# Sheet1.net
KiCad netlist of a schematic drawn in Altium Designer
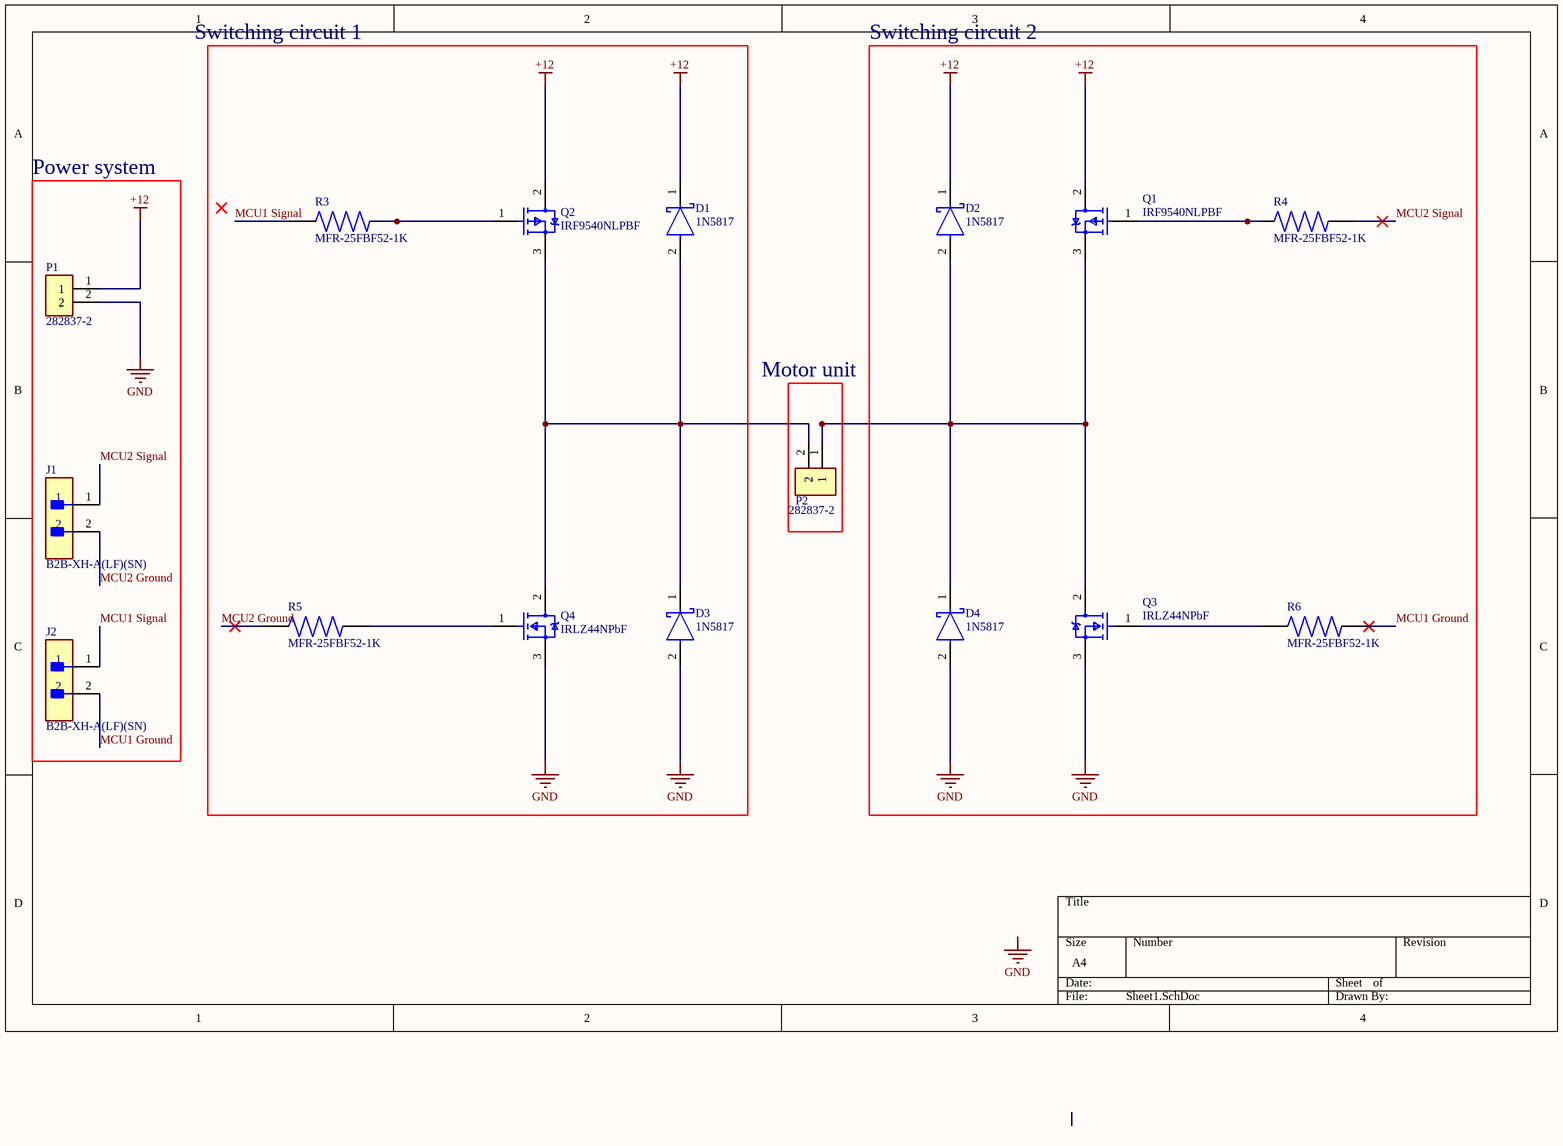
[diagram p0: Sheet1.SchDoc]

(export (version "E")
  (design (tool "Eeschema 10.0.6"))
  (components
    (comp (ref "D1")
      (value "1N5817")
      (footprint "FP-DO-41-MFG")
      (description "DIODE SCHOTTKY 20V 1A DO41")
      (libsource (lib "Altium Content Vault") (part "1d6ec82d83fb6aee721767c19dac4b9"))
    )
    (comp (ref "D2")
      (value "1N5817")
      (footprint "FP-DO-41-MFG")
      (description "DIODE SCHOTTKY 20V 1A DO41")
      (libsource (lib "Altium Content Vault") (part "1d6ec82d83fb6aee721767c19dac4b9"))
    )
    (comp (ref "D3")
      (value "1N5817")
      (footprint "FP-DO-41-MFG")
      (description "DIODE SCHOTTKY 20V 1A DO41")
      (libsource (lib "Altium Content Vault") (part "1d6ec82d83fb6aee721767c19dac4b9"))
    )
    (comp (ref "D4")
      (value "1N5817")
      (footprint "FP-DO-41-MFG")
      (description "DIODE SCHOTTKY 20V 1A DO41")
      (libsource (lib "Altium Content Vault") (part "1d6ec82d83fb6aee721767c19dac4b9"))
    )
    (comp (ref "J1")
      (value "B2B-XH-A(LF)(SN)")
      (footprint "FP-B2B-XH-A_LF_SN-MFG")
      (description "CONN HEADER VERT 2POS 2.5MM")
      (libsource (lib "Altium Content Vault") (part "3bc925449376181038e59eaffc5286c"))
    )
    (comp (ref "J2")
      (value "B2B-XH-A(LF)(SN)")
      (footprint "FP-B2B-XH-A_LF_SN-MFG")
      (description "CONN HEADER VERT 2POS 2.5MM")
      (libsource (lib "Altium Content Vault") (part "3bc925449376181038e59eaffc5286c"))
    )
    (comp (ref "P1")
      (value "282837-2")
      (footprint "TE_282837-2")
      (fields (field (name "MF") "TE Connectivity"))
      (libsource (lib "282837-2 (1)") (part "282837-2"))
    )
    (comp (ref "P2")
      (value "282837-2")
      (footprint "TE_282837-2")
      (fields (field (name "MF") "TE Connectivity"))
      (libsource (lib "282837-2 (1)") (part "282837-2"))
    )
    (comp (ref "Q1")
      (value "IRF9540NLPBF")
      (footprint "FP-PG-TO262-3-MFG")
      (description "MOSFET P-CH 100V 23A TO262-3")
      (libsource (lib "Altium Content Vault") (part "38cbee71a1bce1ebb3b8a3a9639eda0"))
    )
    (comp (ref "Q2")
      (value "IRF9540NLPBF")
      (footprint "FP-PG-TO262-3-MFG")
      (description "MOSFET P-CH 100V 23A TO262-3")
      (libsource (lib "Altium Content Vault") (part "38cbee71a1bce1ebb3b8a3a9639eda0"))
    )
    (comp (ref "Q3")
      (value "IRLZ44NPbF")
      (footprint "FP-PG-TO220-3-MFG")
      (description "MOSFET N-CH 55V 47A TO220AB")
      (libsource (lib "Altium Content Vault") (part "b09f7f152735e370c1ea22a33fa83d6"))
    )
    (comp (ref "Q4")
      (value "IRLZ44NPbF")
      (footprint "FP-PG-TO220-3-MFG")
      (description "MOSFET N-CH 55V 47A TO220AB")
      (libsource (lib "Altium Content Vault") (part "b09f7f152735e370c1ea22a33fa83d6"))
    )
    (comp (ref "R3")
      (value "MFR-25FBF52-1K")
      (footprint "RESAD1100W55L680D260")
      (description "10.2 kOhms Â±1% 0.25W, 1/4W Through Hole Resistor Axial - Metal Film")
      (fields (field (name "MF") "Yageo") (field (name "MP") "MFR-25FBF52-10K"))
      (libsource (lib "MFR-25FBF52-10K (1)") (part "MFR-25FBF52-10K"))
    )
    (comp (ref "R4")
      (value "MFR-25FBF52-1K")
      (footprint "RESAD1100W55L680D260")
      (description "10.2 kOhms Â±1% 0.25W, 1/4W Through Hole Resistor Axial - Metal Film")
      (fields (field (name "MF") "Yageo") (field (name "MP") "MFR-25FBF52-10K"))
      (libsource (lib "MFR-25FBF52-10K (1)") (part "MFR-25FBF52-10K"))
    )
    (comp (ref "R5")
      (value "MFR-25FBF52-1K")
      (footprint "RESAD1100W55L680D260")
      (description "10.2 kOhms Â±1% 0.25W, 1/4W Through Hole Resistor Axial - Metal Film")
      (fields (field (name "MF") "Yageo") (field (name "MP") "MFR-25FBF52-10K"))
      (libsource (lib "MFR-25FBF52-10K (1)") (part "MFR-25FBF52-10K"))
    )
    (comp (ref "R6")
      (value "MFR-25FBF52-1K")
      (footprint "RESAD1100W55L680D260")
      (description "10.2 kOhms Â±1% 0.25W, 1/4W Through Hole Resistor Axial - Metal Film")
      (fields (field (name "MF") "Yageo") (field (name "MP") "MFR-25FBF52-10K"))
      (libsource (lib "MFR-25FBF52-10K (1)") (part "MFR-25FBF52-10K"))
    )
  )
  (nets
    (net (code "1") (name "+12") (class "Default")
      (node (ref "D1") (pin "1") (pinfunction "C_1") (pintype "passive"))
      (node (ref "D2") (pin "1") (pinfunction "C_1") (pintype "passive"))
      (node (ref "P1") (pin "1") (pinfunction "1_1") (pintype "passive"))
      (node (ref "Q1") (pin "2") (pinfunction "Drain_2") (pintype "passive"))
      (node (ref "Q2") (pin "2") (pinfunction "Drain_2") (pintype "passive"))
    )
    (net (code "2") (name "/MCU1 Ground") (class "Default")
      (node (ref "J2") (pin "2") (pinfunction "2_2") (pintype "passive"))
      (node (ref "R6") (pin "2") (pinfunction "2_2") (pintype "passive"))
    )
    (net (code "3") (name "/MCU1 Signal") (class "Default")
      (node (ref "J2") (pin "1") (pinfunction "1_1") (pintype "passive"))
      (node (ref "R3") (pin "1") (pinfunction "1_1") (pintype "passive"))
    )
    (net (code "4") (name "/MCU2 Ground") (class "Default")
      (node (ref "J1") (pin "2") (pinfunction "2_2") (pintype "passive"))
      (node (ref "R5") (pin "1") (pinfunction "1_1") (pintype "passive"))
    )
    (net (code "5") (name "/MCU2 Signal") (class "Default")
      (node (ref "J1") (pin "1") (pinfunction "1_1") (pintype "passive"))
      (node (ref "R4") (pin "2") (pinfunction "2_2") (pintype "passive"))
    )
    (net (code "6") (name "GND") (class "Default")
      (node (ref "D3") (pin "2") (pinfunction "A_2") (pintype "passive"))
      (node (ref "D4") (pin "2") (pinfunction "A_2") (pintype "passive"))
      (node (ref "P1") (pin "2") (pinfunction "2_2") (pintype "passive"))
      (node (ref "Q3") (pin "3") (pinfunction "S_3") (pintype "passive"))
      (node (ref "Q4") (pin "3") (pinfunction "S_3") (pintype "passive"))
    )
    (net (code "7") (name "Net-(D1-A)") (class "Default")
      (node (ref "D1") (pin "2") (pinfunction "A_2") (pintype "passive"))
      (node (ref "D3") (pin "1") (pinfunction "C_1") (pintype "passive"))
      (node (ref "P2") (pin "2") (pinfunction "2_2") (pintype "passive"))
      (node (ref "Q2") (pin "3") (pinfunction "Source_3") (pintype "passive"))
      (node (ref "Q4") (pin "2") (pinfunction "D_2") (pintype "passive"))
    )
    (net (code "8") (name "Net-(D2-A)") (class "Default")
      (node (ref "D2") (pin "2") (pinfunction "A_2") (pintype "passive"))
      (node (ref "D4") (pin "1") (pinfunction "C_1") (pintype "passive"))
      (node (ref "P2") (pin "1") (pinfunction "1_1") (pintype "passive"))
      (node (ref "Q1") (pin "3") (pinfunction "Source_3") (pintype "passive"))
      (node (ref "Q3") (pin "2") (pinfunction "D_2") (pintype "passive"))
    )
    (net (code "9") (name "Net-(Q1-Gate)") (class "Default")
      (node (ref "Q1") (pin "1") (pinfunction "Gate_1") (pintype "passive"))
      (node (ref "R4") (pin "1") (pinfunction "1_1") (pintype "passive"))
    )
    (net (code "10") (name "Net-(Q2-Gate)") (class "Default")
      (node (ref "Q2") (pin "1") (pinfunction "Gate_1") (pintype "passive"))
      (node (ref "R3") (pin "2") (pinfunction "2_2") (pintype "passive"))
    )
    (net (code "11") (name "Net-(Q3-G)") (class "Default")
      (node (ref "Q3") (pin "1") (pinfunction "G_1") (pintype "passive"))
      (node (ref "R6") (pin "1") (pinfunction "1_1") (pintype "passive"))
    )
    (net (code "12") (name "Net-(Q4-G)") (class "Default")
      (node (ref "Q4") (pin "1") (pinfunction "G_1") (pintype "passive"))
      (node (ref "R5") (pin "2") (pinfunction "2_2") (pintype "passive"))
    )
  )
)
